# SmartWatch-V2.net
KiCad netlist of a schematic drawn in Altium Designer
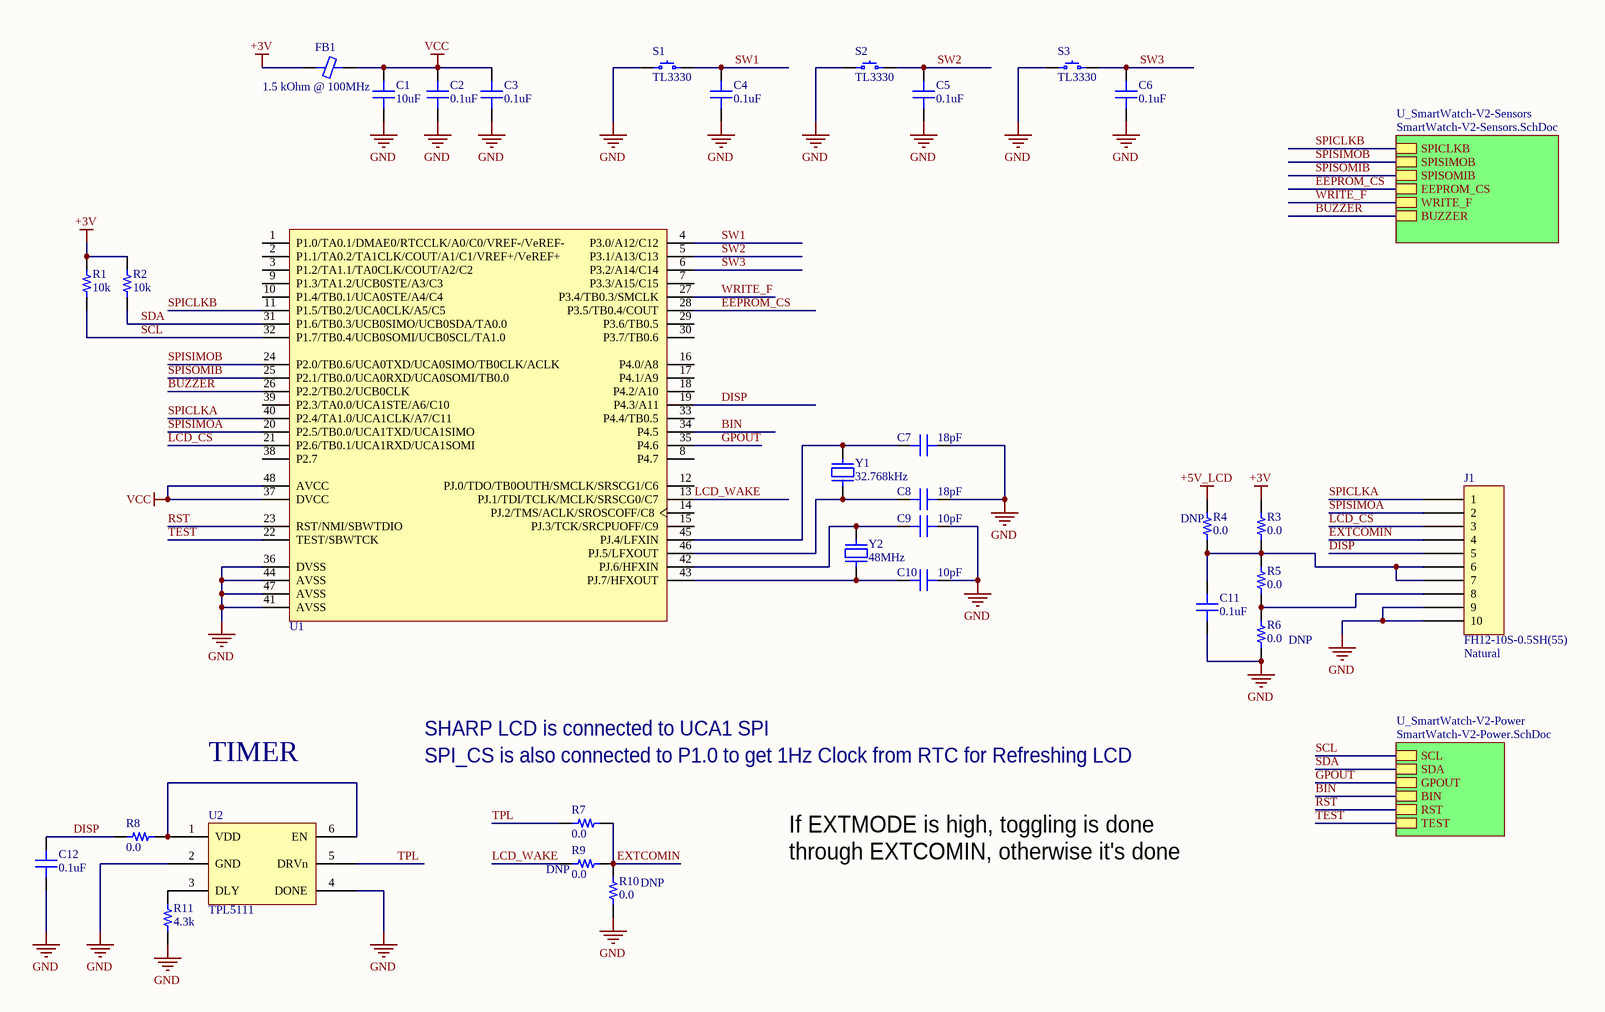
[diagram p0: SmartWatch-V2.SchDoc]

(export (version "E")
  (design (tool "Eeschema 10.0.6"))
  (components
    (comp (ref "C1")
      (value "10uF")
      (footprint "CAP 0603/1608")
      (description "CAP CER 10UF 6.3V X5R 0603")
      (fields
        (field (name "PART NUMBER") "GRM188R60J106ME47D")
        (field (name "MANUFACTURER") "Murata Electronics North America")
      )
      (libsource (lib "Celestial Library Database") (part "Capacitor"))
    )
    (comp (ref "C2")
      (value "0.1uF")
      (footprint "CAP 0402/1005")
      (description "CAP CER 0.1UF 16V X7R 0402")
      (fields
        (field (name "PART NUMBER") "C1005X7R1C104K050BC")
        (field (name "MANUFACTURER") "TDK Corporation")
      )
      (libsource (lib "Celestial Library Database") (part "Capacitor"))
    )
    (comp (ref "C3")
      (value "0.1uF")
      (footprint "CAP 0402/1005")
      (description "CAP CER 0.1UF 16V X7R 0402")
      (fields
        (field (name "PART NUMBER") "C1005X7R1C104K050BC")
        (field (name "MANUFACTURER") "TDK Corporation")
      )
      (libsource (lib "Celestial Library Database") (part "Capacitor"))
    )
    (comp (ref "C4")
      (value "0.1uF")
      (footprint "CAP 0402/1005")
      (description "CAP CER 0.1UF 16V X7R 0402")
      (fields
        (field (name "PART NUMBER") "C1005X7R1C104K050BC")
        (field (name "MANUFACTURER") "TDK Corporation")
      )
      (libsource (lib "Celestial Library Database") (part "Capacitor"))
    )
    (comp (ref "C5")
      (value "0.1uF")
      (footprint "CAP 0402/1005")
      (description "CAP CER 0.1UF 16V X7R 0402")
      (fields
        (field (name "PART NUMBER") "C1005X7R1C104K050BC")
        (field (name "MANUFACTURER") "TDK Corporation")
      )
      (libsource (lib "Celestial Library Database") (part "Capacitor"))
    )
    (comp (ref "C6")
      (value "0.1uF")
      (footprint "CAP 0402/1005")
      (description "CAP CER 0.1UF 16V X7R 0402")
      (fields
        (field (name "PART NUMBER") "C1005X7R1C104K050BC")
        (field (name "MANUFACTURER") "TDK Corporation")
      )
      (libsource (lib "Celestial Library Database") (part "Capacitor"))
    )
    (comp (ref "C7")
      (value "18pF")
      (footprint "CAP 0402/1005")
      (description "CAP CER 18PF 50V C0G 0402")
      (fields
        (field (name "PART NUMBER") "C1005C0G1H180J050BA")
        (field (name "MANUFACTURER") "TDK Corporation")
      )
      (libsource (lib "Celestial Library Database") (part "Capacitor"))
    )
    (comp (ref "C8")
      (value "18pF")
      (footprint "CAP 0402/1005")
      (description "CAP CER 18PF 50V C0G 0402")
      (fields
        (field (name "PART NUMBER") "C1005C0G1H180J050BA")
        (field (name "MANUFACTURER") "TDK Corporation")
      )
      (libsource (lib "Celestial Library Database") (part "Capacitor"))
    )
    (comp (ref "C9")
      (value "10pF")
      (footprint "CAP 0402/1005")
      (description "CAP CER 10PF 50V C0G 0402")
      (fields
        (field (name "PART NUMBER") "C1005C0G1H100D050BA")
        (field (name "MANUFACTURER") "TDK Corporation")
      )
      (libsource (lib "Celestial Library Database") (part "Capacitor"))
    )
    (comp (ref "C10")
      (value "10pF")
      (footprint "CAP 0402/1005")
      (description "CAP CER 10PF 50V C0G 0402")
      (fields
        (field (name "PART NUMBER") "C1005C0G1H100D050BA")
        (field (name "MANUFACTURER") "TDK Corporation")
      )
      (libsource (lib "Celestial Library Database") (part "Capacitor"))
    )
    (comp (ref "C11")
      (value "0.1uF")
      (footprint "CAP 0402/1005")
      (description "CAP CER 0.1UF 16V X7R 0402")
      (fields
        (field (name "PART NUMBER") "C1005X7R1C104K050BC")
        (field (name "MANUFACTURER") "TDK Corporation")
      )
      (libsource (lib "Celestial Library Database") (part "Capacitor"))
    )
    (comp (ref "C12")
      (value "0.1uF")
      (footprint "CAP 0402/1005")
      (description "CAP CER 0.1UF 16V X7R 0402")
      (fields
        (field (name "PART NUMBER") "C1005X7R1C104K050BC")
        (field (name "MANUFACTURER") "TDK Corporation")
      )
      (libsource (lib "Celestial Library Database") (part "Capacitor"))
    )
    (comp (ref "FB1")
      (value "1.5 kOhm @ 100MHz")
      (footprint "FER 0603/1608")
      (description "FERRITE CHIP 1500 OHM 500MA 0603")
      (fields
        (field (name "PART NUMBER") "BLM18HE152SN1D")
        (field (name "MANUFACTURER") "Murata Electronics North America")
      )
      (libsource (lib "Celestial Library Database") (part "Ferrite Chip"))
    )
    (comp (ref "J1")
      (value "FH12-10S-0.5SH(55)")
      (footprint "FH12-10S-0.5SH(55)")
      (description "CONN FFC BOTTOM 10POS 0.50MM R/A")
      (fields (field (name "COLOUR") "Natural"))
      (libsource (lib "Celestial Library Database") (part "10 Pin"))
    )
    (comp (ref "R1")
      (value "10k")
      (footprint "RES 0402/1005")
      (description "RES SMD 10K OHM 0.5% 1/16W 0402")
      (fields
        (field (name "PART NUMBER") "ERA-2AED103X")
        (field (name "MANUFACTURER") "Panasonic Electronic Components")
      )
      (libsource (lib "Celestial Library Database") (part "Resistor"))
    )
    (comp (ref "R2")
      (value "10k")
      (footprint "RES 0402/1005")
      (description "RES SMD 10K OHM 0.5% 1/16W 0402")
      (fields
        (field (name "PART NUMBER") "ERA-2AED103X")
        (field (name "MANUFACTURER") "Panasonic Electronic Components")
      )
      (libsource (lib "Celestial Library Database") (part "Resistor"))
    )
    (comp (ref "R3")
      (value "0.0")
      (footprint "RES 0603/1608")
      (description "RES SMD 0.0OHM JUMPER 1/10W 0603")
      (fields
        (field (name "PART NUMBER") "ERJ-3GEY0R00V")
        (field (name "MANUFACTURER") "Panasonic Electronic Components")
      )
      (libsource (lib "Celestial Library Database") (part "Resistor"))
    )
    (comp (ref "R4")
      (value "0.0")
      (footprint "RES 0603/1608")
      (description "RES SMD 0.0OHM JUMPER 1/10W 0603")
      (fields
        (field (name "PART NUMBER") "ERJ-3GEY0R00V")
        (field (name "MANUFACTURER") "Panasonic Electronic Components")
      )
      (libsource (lib "Celestial Library Database") (part "Resistor"))
    )
    (comp (ref "R5")
      (value "0.0")
      (footprint "RES 0603/1608")
      (description "RES SMD 0.0OHM JUMPER 1/10W 0603")
      (fields
        (field (name "PART NUMBER") "ERJ-3GEY0R00V")
        (field (name "MANUFACTURER") "Panasonic Electronic Components")
      )
      (libsource (lib "Celestial Library Database") (part "Resistor"))
    )
    (comp (ref "R6")
      (value "0.0")
      (footprint "RES 0603/1608")
      (description "DNP")
      (fields
        (field (name "PART NUMBER") "ERJ-3GEY0R00V")
        (field (name "MANUFACTURER") "Panasonic Electronic Components")
      )
      (libsource (lib "Celestial Library Database") (part "Resistor"))
    )
    (comp (ref "R7")
      (value "0.0")
      (footprint "RES 0603/1608")
      (description "RES SMD 0.0OHM JUMPER 1/10W 0603")
      (fields
        (field (name "PART NUMBER") "ERJ-3GEY0R00V")
        (field (name "MANUFACTURER") "Panasonic Electronic Components")
      )
      (libsource (lib "Celestial Library Database") (part "Resistor"))
    )
    (comp (ref "R8")
      (value "0.0")
      (footprint "RES 0603/1608")
      (description "RES SMD 0.0OHM JUMPER 1/10W 0603")
      (fields
        (field (name "PART NUMBER") "ERJ-3GEY0R00V")
        (field (name "MANUFACTURER") "Panasonic Electronic Components")
      )
      (libsource (lib "Celestial Library Database") (part "Resistor"))
    )
    (comp (ref "R9")
      (value "0.0")
      (footprint "RES 0603/1608")
      (description "DNP")
      (fields
        (field (name "PART NUMBER") "ERJ-3GEY0R00V")
        (field (name "MANUFACTURER") "Panasonic Electronic Components")
      )
      (libsource (lib "Celestial Library Database") (part "Resistor"))
    )
    (comp (ref "R10")
      (value "0.0")
      (footprint "RES 0603/1608")
      (description "DNP")
      (fields
        (field (name "PART NUMBER") "ERJ-3GEY0R00V")
        (field (name "MANUFACTURER") "Panasonic Electronic Components")
      )
      (libsource (lib "Celestial Library Database") (part "Resistor"))
    )
    (comp (ref "R11")
      (value "4.3k")
      (footprint "RES 0603/1608")
      (description "RES SMD 4.3K OHM 0.1% 1/10W 0603")
      (fields
        (field (name "PART NUMBER") "ERA-3AEB432V")
        (field (name "MANUFACTURER") "Panasonic Electronic Components")
      )
      (libsource (lib "Celestial Library Database") (part "Resistor"))
    )
    (comp (ref "S1")
      (value "TL3330")
      (footprint "TL3330")
      (description "SWITCH TACTILE SPST-NO 0.02A 15V")
      (fields (field (name "MANUFACTURER") "E-Switch"))
      (libsource (lib "Celestial Library Database") (part "SPST-NO 2 PIN"))
    )
    (comp (ref "S2")
      (value "TL3330")
      (footprint "TL3330")
      (description "SWITCH TACTILE SPST-NO 0.02A 15V")
      (fields (field (name "MANUFACTURER") "E-Switch"))
      (libsource (lib "Celestial Library Database") (part "SPST-NO 2 PIN"))
    )
    (comp (ref "S3")
      (value "TL3330")
      (footprint "TL3330")
      (description "SWITCH TACTILE SPST-NO 0.02A 15V")
      (fields (field (name "MANUFACTURER") "E-Switch"))
      (libsource (lib "Celestial Library Database") (part "SPST-NO 2 PIN"))
    )
    (comp (ref "U1")
      (value "MSP430FR5969IRGZ")
      (footprint "TI-RGZ48-4100X4100TP_N")
      (description "16BIT 64KB FRAM 48VQFN")
      (fields (field (name "MANUFACTURER") "Texas Instruments") (field (name "PARTNUMBER") "MSP430FR5969RGZ"))
      (libsource (lib "Celestial Library Database") (part "MSP430FR5969IRGZ"))
    )
    (comp (ref "U2")
      (value "TPL5111")
      (footprint "TI SOT-23-6 DDC")
      (libsource (lib "Altium Component") (part "TPL5111"))
    )
    (comp (ref "Y1")
      (value "32.768kHz")
      (footprint "ABRACON ABS07")
      (description "CRYSTAL 32.7680KHZ 6PF SMD")
      (fields
        (field (name "PART NUMBER") "ABS07-120-32.768KHZ-T")
        (field (name "MANUFACTURER") "Abracon LLC")
      )
      (libsource (lib "Celestial Library Database") (part "Abracon Crystal ABS07"))
    )
    (comp (ref "Y2")
      (value "48MHz")
      (footprint "Kyocera CX3225GB")
      (description "CRYSTAL 48.0000MHZ 8PF SMD")
      (fields
        (field (name "PART NUMBER") "CX3225GB48000D0HPQCC")
        (field (name "MANUFACTURER") "AVX Corp/Kyocera Corp")
      )
      (libsource (lib "Celestial Library Database") (part "Kyocera Crystal CX3225GB"))
    )
  )
  (nets
    (net (code "1") (name "+3V") (class "Default")
      (node (ref "FB1") (pin "1") (pinfunction "1_1") (pintype "passive"))
      (node (ref "R1") (pin "2") (pinfunction "2_2") (pintype "passive"))
      (node (ref "R2") (pin "2") (pinfunction "2_2") (pintype "passive"))
      (node (ref "R3") (pin "2") (pinfunction "2_2") (pintype "passive"))
    )
    (net (code "2") (name "+5V_LCD") (class "Default")
      (node (ref "R4") (pin "2") (pinfunction "2_2") (pintype "passive"))
    )
    (net (code "3") (name "/BIN") (class "Default")
      (node (ref "U1") (pin "34") (pinfunction "P4.5_34") (pintype "passive"))
    )
    (net (code "4") (name "/BUZZER") (class "Default")
      (node (ref "U1") (pin "26") (pinfunction "P2.2/TB0.2/UCB0CLK_26") (pintype "passive"))
    )
    (net (code "5") (name "/DISP") (class "Default")
      (node (ref "C12") (pin "2") (pinfunction "2_2") (pintype "passive"))
      (node (ref "J1") (pin "5") (pinfunction "5_5") (pintype "passive"))
      (node (ref "R8") (pin "2") (pinfunction "2_2") (pintype "passive"))
      (node (ref "U1") (pin "19") (pinfunction "P4.3/A11_19") (pintype "passive"))
    )
    (net (code "6") (name "/EEPROM_CS") (class "Default")
      (node (ref "U1") (pin "28") (pinfunction "P3.5/TB0.4/COUT_28") (pintype "passive"))
    )
    (net (code "7") (name "/EXTCOMIN") (class "Default")
      (node (ref "J1") (pin "4") (pinfunction "4_4") (pintype "passive"))
      (node (ref "R10") (pin "2") (pinfunction "2_2") (pintype "passive"))
      (node (ref "R7") (pin "1") (pinfunction "1_1") (pintype "passive"))
      (node (ref "R9") (pin "1") (pinfunction "1_1") (pintype "passive"))
    )
    (net (code "8") (name "/GPOUT") (class "Default")
      (node (ref "U1") (pin "35") (pinfunction "P4.6_35") (pintype "passive"))
    )
    (net (code "9") (name "/LCD_CS") (class "Default")
      (node (ref "J1") (pin "3") (pinfunction "3_3") (pintype "passive"))
      (node (ref "U1") (pin "21") (pinfunction "P2.6/TB0.1/UCA1RXD/UCA1SOMI_21") (pintype "passive"))
    )
    (net (code "10") (name "/LCD_WAKE") (class "Default")
      (node (ref "R9") (pin "2") (pinfunction "2_2") (pintype "passive"))
      (node (ref "U1") (pin "13") (pinfunction "PJ.1/TDI/TCLK/MCLK/SRSCG0/C7_13") (pintype "passive"))
    )
    (net (code "11") (name "/RST") (class "Default")
      (node (ref "U1") (pin "23") (pinfunction "RST/NMI/SBWTDIO_23") (pintype "passive"))
    )
    (net (code "12") (name "/SCL") (class "Default")
      (node (ref "R1") (pin "1") (pinfunction "1_1") (pintype "passive"))
      (node (ref "U1") (pin "32") (pinfunction "P1.7/TB0.4/UCB0SOMI/UCB0SCL/TA1.0_32") (pintype "power_in"))
    )
    (net (code "13") (name "/SDA") (class "Default")
      (node (ref "R2") (pin "1") (pinfunction "1_1") (pintype "passive"))
      (node (ref "U1") (pin "31") (pinfunction "P1.6/TB0.3/UCB0SIMO/UCB0SDA/TA0.0_31") (pintype "power_in"))
    )
    (net (code "14") (name "/SPICLKA") (class "Default")
      (node (ref "J1") (pin "1") (pinfunction "1_1") (pintype "passive"))
      (node (ref "U1") (pin "40") (pinfunction "P2.4/TA1.0/UCA1CLK/A7/C11_40") (pintype "power_in"))
    )
    (net (code "15") (name "/SPICLKB") (class "Default")
      (node (ref "U1") (pin "11") (pinfunction "P1.5/TB0.2/UCA0CLK/A5/C5_11") (pintype "passive"))
    )
    (net (code "16") (name "/SPISIMOA") (class "Default")
      (node (ref "J1") (pin "2") (pinfunction "2_2") (pintype "passive"))
      (node (ref "U1") (pin "20") (pinfunction "P2.5/TB0.0/UCA1TXD/UCA1SIMO_20") (pintype "passive"))
    )
    (net (code "17") (name "/SPISIMOB") (class "Default")
      (node (ref "U1") (pin "24") (pinfunction "P2.0/TB0.6/UCA0TXD/UCA0SIMO/TB0CLK/ACLK_24") (pintype "passive"))
    )
    (net (code "18") (name "/SPISOMIB") (class "Default")
      (node (ref "U1") (pin "25") (pinfunction "P2.1/TB0.0/UCA0RXD/UCA0SOMI/TB0.0_25") (pintype "passive"))
    )
    (net (code "19") (name "/SW1") (class "Default")
      (node (ref "C4") (pin "2") (pinfunction "2_2") (pintype "passive"))
      (node (ref "S1") (pin "2") (pinfunction "2_2") (pintype "passive"))
      (node (ref "U1") (pin "4") (pinfunction "P3.0/A12/C12_4") (pintype "passive"))
    )
    (net (code "20") (name "/SW2") (class "Default")
      (node (ref "C5") (pin "2") (pinfunction "2_2") (pintype "passive"))
      (node (ref "S2") (pin "2") (pinfunction "2_2") (pintype "passive"))
      (node (ref "U1") (pin "5") (pinfunction "P3.1/A13/C13_5") (pintype "passive"))
    )
    (net (code "21") (name "/SW3") (class "Default")
      (node (ref "C6") (pin "2") (pinfunction "2_2") (pintype "passive"))
      (node (ref "S3") (pin "2") (pinfunction "2_2") (pintype "passive"))
      (node (ref "U1") (pin "6") (pinfunction "P3.2/A14/C14_6") (pintype "passive"))
    )
    (net (code "22") (name "/TEST") (class "Default")
      (node (ref "U1") (pin "22") (pinfunction "TEST/SBWTCK_22") (pintype "passive"))
    )
    (net (code "23") (name "/TPL") (class "Default")
      (node (ref "R7") (pin "2") (pinfunction "2_2") (pintype "passive"))
      (node (ref "U2") (pin "5") (pinfunction "DRVn_5") (pintype "passive"))
    )
    (net (code "24") (name "/WRITE_F") (class "Default")
      (node (ref "U1") (pin "27") (pinfunction "P3.4/TB0.3/SMCLK_27") (pintype "passive"))
    )
    (net (code "25") (name "GND") (class "Default")
      (node (ref "C1") (pin "1") (pinfunction "1_1") (pintype "passive"))
      (node (ref "C10") (pin "2") (pinfunction "2_2") (pintype "passive"))
      (node (ref "C11") (pin "1") (pinfunction "1_1") (pintype "passive"))
      (node (ref "C12") (pin "1") (pinfunction "1_1") (pintype "passive"))
      (node (ref "C2") (pin "1") (pinfunction "1_1") (pintype "passive"))
      (node (ref "C3") (pin "1") (pinfunction "1_1") (pintype "passive"))
      (node (ref "C4") (pin "1") (pinfunction "1_1") (pintype "passive"))
      (node (ref "C5") (pin "1") (pinfunction "1_1") (pintype "passive"))
      (node (ref "C6") (pin "1") (pinfunction "1_1") (pintype "passive"))
      (node (ref "C7") (pin "2") (pinfunction "2_2") (pintype "passive"))
      (node (ref "C8") (pin "2") (pinfunction "2_2") (pintype "passive"))
      (node (ref "C9") (pin "2") (pinfunction "2_2") (pintype "passive"))
      (node (ref "J1") (pin "10") (pinfunction "10_10") (pintype "passive"))
      (node (ref "J1") (pin "9") (pinfunction "9_9") (pintype "passive"))
      (node (ref "R10") (pin "1") (pinfunction "1_1") (pintype "passive"))
      (node (ref "R11") (pin "1") (pinfunction "1_1") (pintype "passive"))
      (node (ref "R6") (pin "1") (pinfunction "1_1") (pintype "passive"))
      (node (ref "S1") (pin "1") (pinfunction "1_1") (pintype "passive"))
      (node (ref "S2") (pin "1") (pinfunction "1_1") (pintype "passive"))
      (node (ref "S3") (pin "1") (pinfunction "1_1") (pintype "passive"))
      (node (ref "U1") (pin "36") (pinfunction "DVSS_36") (pintype "power_in"))
      (node (ref "U1") (pin "41") (pinfunction "AVSS_41") (pintype "power_in"))
      (node (ref "U1") (pin "44") (pinfunction "AVSS_44") (pintype "passive"))
      (node (ref "U1") (pin "47") (pinfunction "AVSS_47") (pintype "passive"))
      (node (ref "U2") (pin "2") (pinfunction "GND_2") (pintype "passive"))
      (node (ref "U2") (pin "4") (pinfunction "DONE_4") (pintype "passive"))
    )
    (net (code "26") (name "Net-(C11-Pad2)") (class "Default")
      (node (ref "C11") (pin "2") (pinfunction "2_2") (pintype "passive"))
      (node (ref "J1") (pin "6") (pinfunction "6_6") (pintype "passive"))
      (node (ref "J1") (pin "7") (pinfunction "7_7") (pintype "passive"))
      (node (ref "R3") (pin "1") (pinfunction "1_1") (pintype "passive"))
      (node (ref "R4") (pin "1") (pinfunction "1_1") (pintype "passive"))
      (node (ref "R5") (pin "2") (pinfunction "2_2") (pintype "passive"))
    )
    (net (code "27") (name "Net-(J1-Pad8)") (class "Default")
      (node (ref "J1") (pin "8") (pinfunction "8_8") (pintype "passive"))
      (node (ref "R5") (pin "1") (pinfunction "1_1") (pintype "passive"))
      (node (ref "R6") (pin "2") (pinfunction "2_2") (pintype "passive"))
    )
    (net (code "28") (name "Net-(U1-PJ.4{slash}LFXIN)") (class "Default")
      (node (ref "C7") (pin "1") (pinfunction "1_1") (pintype "passive"))
      (node (ref "U1") (pin "45") (pinfunction "PJ.4/LFXIN_45") (pintype "passive"))
      (node (ref "Y1") (pin "2") (pinfunction "2_2") (pintype "passive"))
    )
    (net (code "29") (name "Net-(U1-PJ.5{slash}LFXOUT)") (class "Default")
      (node (ref "C8") (pin "1") (pinfunction "1_1") (pintype "passive"))
      (node (ref "U1") (pin "46") (pinfunction "PJ.5/LFXOUT_46") (pintype "passive"))
      (node (ref "Y1") (pin "1") (pinfunction "1_1") (pintype "passive"))
    )
    (net (code "30") (name "Net-(U1-PJ.6{slash}HFXIN)") (class "Default")
      (node (ref "C9") (pin "1") (pinfunction "1_1") (pintype "passive"))
      (node (ref "U1") (pin "42") (pinfunction "PJ.6/HFXIN_42") (pintype "passive"))
      (node (ref "Y2") (pin "3") (pinfunction "3_3") (pintype "passive"))
    )
    (net (code "31") (name "Net-(U1-PJ.7{slash}HFXOUT)") (class "Default")
      (node (ref "C10") (pin "1") (pinfunction "1_1") (pintype "passive"))
      (node (ref "U1") (pin "43") (pinfunction "PJ.7/HFXOUT_43") (pintype "passive"))
      (node (ref "Y2") (pin "1") (pinfunction "1_1") (pintype "passive"))
    )
    (net (code "32") (name "Net-(U2-DLY)") (class "Default")
      (node (ref "R11") (pin "2") (pinfunction "2_2") (pintype "passive"))
      (node (ref "U2") (pin "3") (pinfunction "DLY_3") (pintype "passive"))
    )
    (net (code "33") (name "Net-(U2-EN)") (class "Default")
      (node (ref "R8") (pin "1") (pinfunction "1_1") (pintype "passive"))
      (node (ref "U2") (pin "1") (pinfunction "VDD_1") (pintype "passive"))
      (node (ref "U2") (pin "6") (pinfunction "EN_6") (pintype "passive"))
    )
    (net (code "34") (name "VCC") (class "Default")
      (node (ref "C1") (pin "2") (pinfunction "2_2") (pintype "passive"))
      (node (ref "C2") (pin "2") (pinfunction "2_2") (pintype "passive"))
      (node (ref "C3") (pin "2") (pinfunction "2_2") (pintype "passive"))
      (node (ref "FB1") (pin "2") (pinfunction "2_2") (pintype "passive"))
      (node (ref "U1") (pin "37") (pinfunction "DVCC_37") (pintype "passive"))
      (node (ref "U1") (pin "48") (pinfunction "AVCC_48") (pintype "passive"))
    )
    (net (code "35") (name "unconnected-(U1-P1.0{slash}TA0.1{slash}DMAE0{slash}RTCCLK{slash}A0{slash}C0{slash}VREF-{slash}VeREF--Pad1)") (class "Default")
      (node (ref "U1") (pin "1") (pinfunction "P1.0/TA0.1/DMAE0/RTCCLK/A0/C0/VREF-/VeREF-_1") (pintype "passive"))
    )
    (net (code "36") (name "unconnected-(U1-P1.1{slash}TA0.2{slash}TA1CLK{slash}COUT{slash}A1{slash}C1{slash}VREF+{slash}VeREF+-Pad2)") (class "Default")
      (node (ref "U1") (pin "2") (pinfunction "P1.1/TA0.2/TA1CLK/COUT/A1/C1/VREF+/VeREF+_2") (pintype "passive"))
    )
    (net (code "37") (name "unconnected-(U1-P1.2{slash}TA1.1{slash}TA0CLK{slash}COUT{slash}A2{slash}C2-Pad3)") (class "Default")
      (node (ref "U1") (pin "3") (pinfunction "P1.2/TA1.1/TA0CLK/COUT/A2/C2_3") (pintype "passive"))
    )
    (net (code "38") (name "unconnected-(U1-P1.3{slash}TA1.2{slash}UCB0STE{slash}A3{slash}C3-Pad9)") (class "Default")
      (node (ref "U1") (pin "9") (pinfunction "P1.3/TA1.2/UCB0STE/A3/C3_9") (pintype "passive"))
    )
    (net (code "39") (name "unconnected-(U1-P1.4{slash}TB0.1{slash}UCA0STE{slash}A4{slash}C4-Pad10)") (class "Default")
      (node (ref "U1") (pin "10") (pinfunction "P1.4/TB0.1/UCA0STE/A4/C4_10") (pintype "passive"))
    )
    (net (code "40") (name "unconnected-(U1-P2.3{slash}TA0.0{slash}UCA1STE{slash}A6{slash}C10-Pad39)") (class "Default")
      (node (ref "U1") (pin "39") (pinfunction "P2.3/TA0.0/UCA1STE/A6/C10_39") (pintype "power_in"))
    )
    (net (code "41") (name "unconnected-(U1-P2.7-Pad38)") (class "Default")
      (node (ref "U1") (pin "38") (pinfunction "P2.7_38") (pintype "passive"))
    )
    (net (code "42") (name "unconnected-(U1-P3.3{slash}A15{slash}C15-Pad7)") (class "Default")
      (node (ref "U1") (pin "7") (pinfunction "P3.3/A15/C15_7") (pintype "passive"))
    )
    (net (code "43") (name "unconnected-(U1-P3.6{slash}TB0.5-Pad29)") (class "Default")
      (node (ref "U1") (pin "29") (pinfunction "P3.6/TB0.5_29") (pintype "passive"))
    )
    (net (code "44") (name "unconnected-(U1-P3.7{slash}TB0.6-Pad30)") (class "Default")
      (node (ref "U1") (pin "30") (pinfunction "P3.7/TB0.6_30") (pintype "passive"))
    )
    (net (code "45") (name "unconnected-(U1-P4.0{slash}A8-Pad16)") (class "Default")
      (node (ref "U1") (pin "16") (pinfunction "P4.0/A8_16") (pintype "passive"))
    )
    (net (code "46") (name "unconnected-(U1-P4.1{slash}A9-Pad17)") (class "Default")
      (node (ref "U1") (pin "17") (pinfunction "P4.1/A9_17") (pintype "passive"))
    )
    (net (code "47") (name "unconnected-(U1-P4.2{slash}A10-Pad18)") (class "Default")
      (node (ref "U1") (pin "18") (pinfunction "P4.2/A10_18") (pintype "passive"))
    )
    (net (code "48") (name "unconnected-(U1-P4.4{slash}TB0.5-Pad33)") (class "Default")
      (node (ref "U1") (pin "33") (pinfunction "P4.4/TB0.5_33") (pintype "passive"))
    )
    (net (code "49") (name "unconnected-(U1-P4.7-Pad8)") (class "Default")
      (node (ref "U1") (pin "8") (pinfunction "P4.7_8") (pintype "passive"))
    )
    (net (code "50") (name "unconnected-(U1-PJ.0{slash}TDO{slash}TB0OUTH{slash}SMCLK{slash}SRSCG1{slash}C6-Pad12)") (class "Default")
      (node (ref "U1") (pin "12") (pinfunction "PJ.0/TDO/TB0OUTH/SMCLK/SRSCG1/C6_12") (pintype "passive"))
    )
    (net (code "51") (name "unconnected-(U1-PJ.2{slash}TMS{slash}ACLK{slash}SROSCOFF{slash}C8-Pad14)") (class "Default")
      (node (ref "U1") (pin "14") (pinfunction "PJ.2/TMS/ACLK/SROSCOFF/C8_14") (pintype "passive"))
    )
    (net (code "52") (name "unconnected-(U1-PJ.3{slash}TCK{slash}SRCPUOFF{slash}C9-Pad15)") (class "Default")
      (node (ref "U1") (pin "15") (pinfunction "PJ.3/TCK/SRCPUOFF/C9_15") (pintype "passive"))
    )
  )
)
